# AmbaSat-05-ZMOD4410.net
KiCad netlist of a schematic drawn in EAGLE
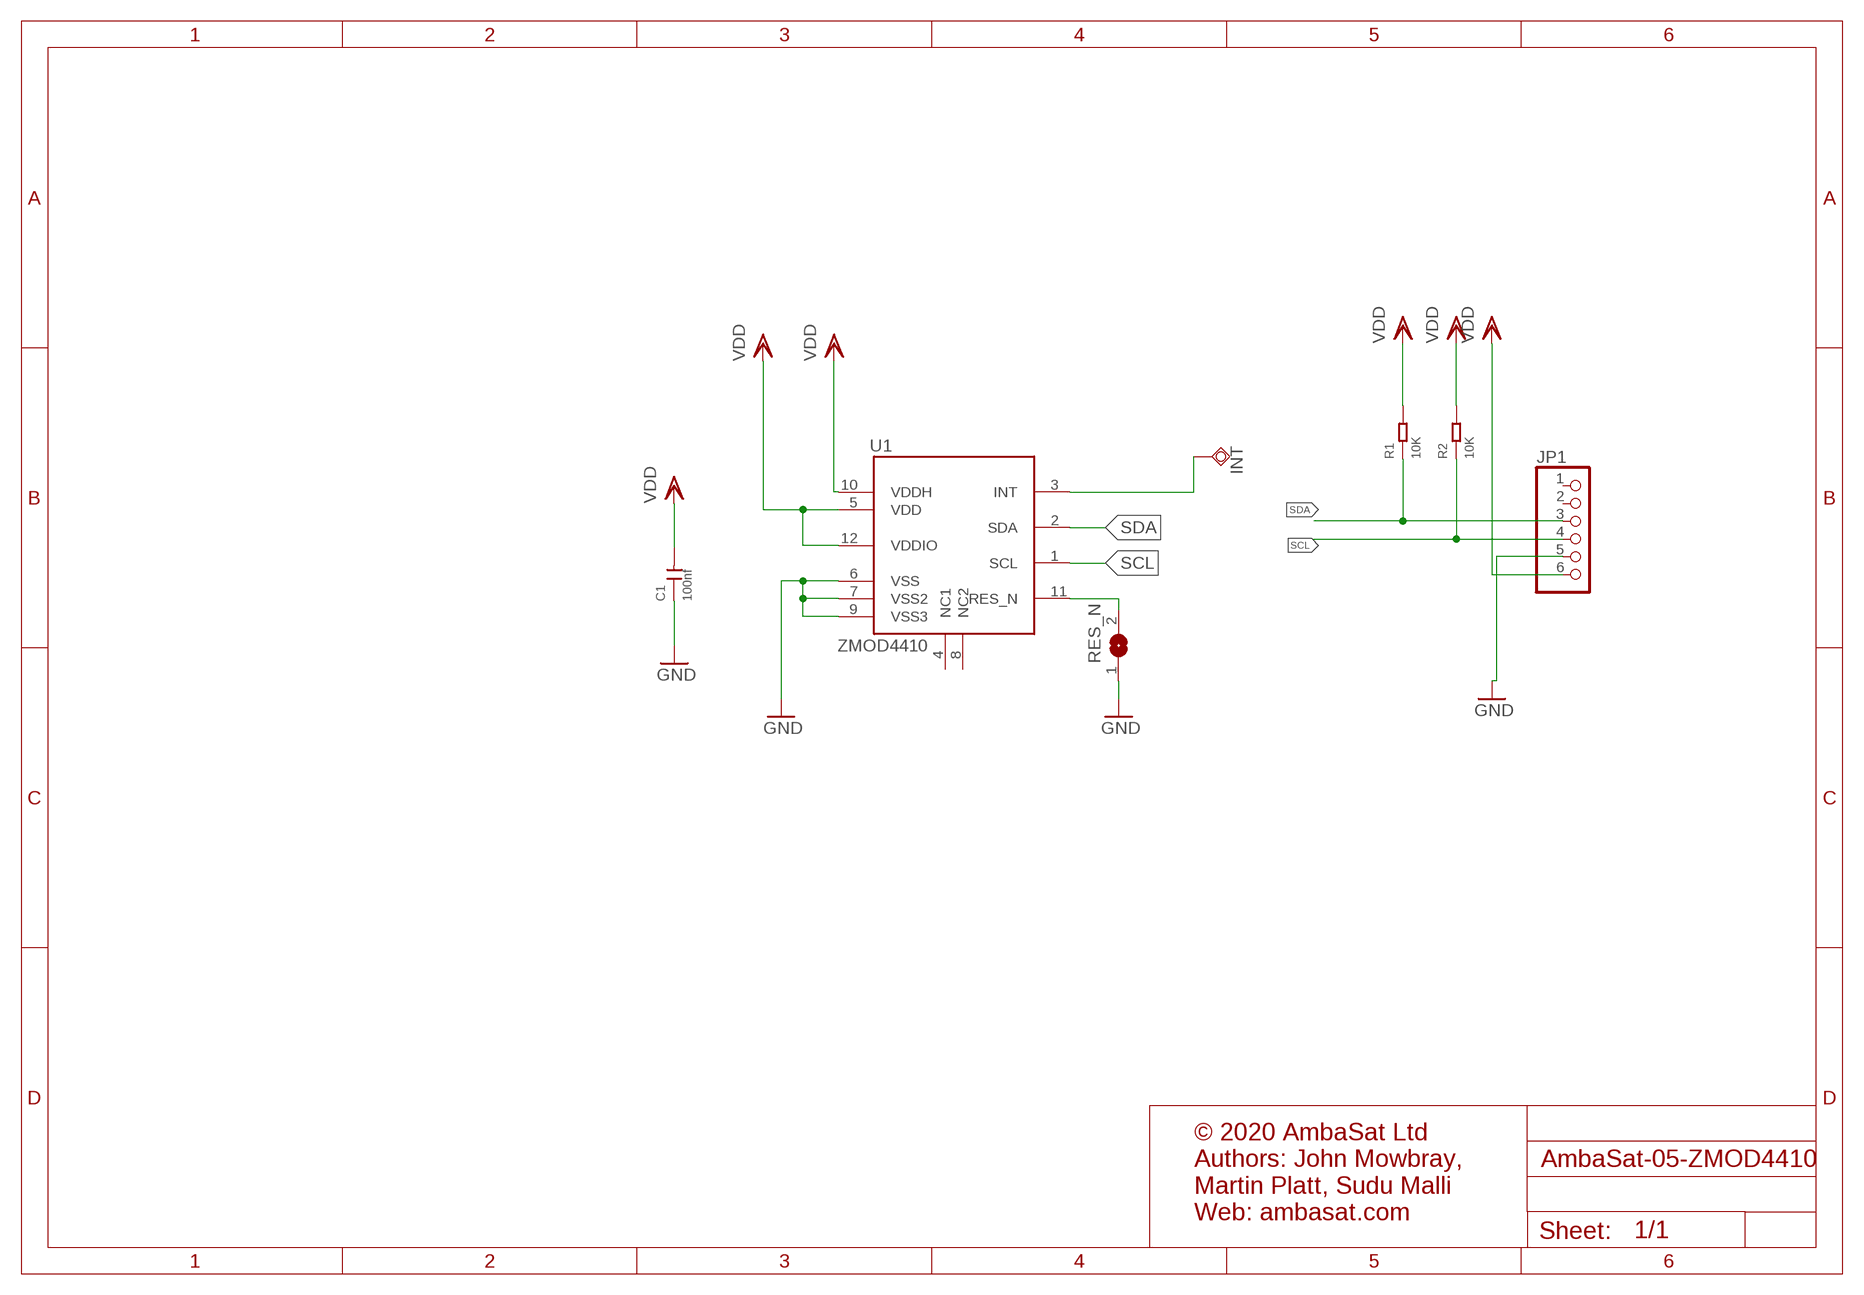
[diagram p0: schematic, sheet 1]

(export (version "E")
  (design (tool "Eeschema 10.0.6"))
  (components
    (comp (ref "C1")
      (value "100nf")
      (footprint "eagle-import:C0805")
      (fields (field (name "MPN") "CC0805KRX7R9BB104"))
      (libsource (lib "eagle-import") (part "CERAMIC-100NF-50V-10%-X7R(0805)"))
    )
    (comp (ref "INT")
      (value "TESTPAD_TPSQTP12R")
      (footprint "eagle-import:TESTPAD_TP12R")
      (libsource (lib "eagle-import") (part "TESTPAD_TPSQTP12R"))
    )
    (comp (ref "JP1")
      (value "HEADER-1X6")
      (footprint "eagle-import:1X06_OVAL")
      (libsource (lib "eagle-import") (part "HEADER-1X6"))
    )
    (comp (ref "R1")
      (value "10K")
      (footprint "eagle-import:R0805")
      (fields (field (name "MPN") "RC0805FR-0710KL"))
      (libsource (lib "eagle-import") (part "SMD-RES-10K-1%-1/8W(0805)"))
    )
    (comp (ref "R2")
      (value "10K")
      (footprint "eagle-import:R0805")
      (fields (field (name "MPN") "RC0805FR-0710KL"))
      (libsource (lib "eagle-import") (part "SMD-RES-10K-1%-1/8W(0805)"))
    )
    (comp (ref "RES_N")
      (value "SJ")
      (footprint "eagle-import:SJ")
      (libsource (lib "eagle-import") (part "SJ"))
    )
    (comp (ref "U1")
      (value "ZMOD4410")
      (footprint "eagle-import:LGG12D1_3X3X0.7_0.5X1")
      (fields
        (field (name "MANUFACTURER") "IDT, Integrated Device Technology Inc")
        (field (name "MPN") "ZMOD4410AI1V")
      )
      (libsource (lib "eagle-import") (part "ZMOD4410"))
    )
  )
  (nets
    (net (code "1") (name "GND") (class "Default")
      (node (ref "C1") (pin "1") (pinfunction "1_1") (pintype "passive"))
      (node (ref "JP1") (pin "5") (pinfunction "5_5") (pintype "passive"))
      (node (ref "RES_N") (pin "1") (pinfunction "1_1") (pintype "passive"))
      (node (ref "U1") (pin "6") (pinfunction "VSS_6") (pintype "power_in"))
      (node (ref "U1") (pin "7") (pinfunction "VSS2_7") (pintype "bidirectional"))
      (node (ref "U1") (pin "9") (pinfunction "VSS3_9") (pintype "bidirectional"))
    )
    (net (code "2") (name "Net-(U1-INT)") (class "Default")
      (node (ref "INT") (pin "TP") (pinfunction "TP_TP") (pintype "input"))
      (node (ref "U1") (pin "3") (pinfunction "INT_3") (pintype "bidirectional"))
    )
    (net (code "3") (name "Net-(U1-RES_N)") (class "Default")
      (node (ref "RES_N") (pin "2") (pinfunction "2_2") (pintype "passive"))
      (node (ref "U1") (pin "11") (pinfunction "RES_N_11") (pintype "bidirectional"))
    )
    (net (code "4") (name "SCL") (class "Default")
      (node (ref "JP1") (pin "4") (pinfunction "4_4") (pintype "passive"))
      (node (ref "R2") (pin "1") (pinfunction "1_1") (pintype "passive"))
      (node (ref "U1") (pin "1") (pinfunction "SCL_1") (pintype "input"))
    )
    (net (code "5") (name "SDA") (class "Default")
      (node (ref "JP1") (pin "3") (pinfunction "3_3") (pintype "passive"))
      (node (ref "R1") (pin "1") (pinfunction "1_1") (pintype "passive"))
      (node (ref "U1") (pin "2") (pinfunction "SDA_2") (pintype "bidirectional"))
    )
    (net (code "6") (name "VDD") (class "Default")
      (node (ref "C1") (pin "2") (pinfunction "2_2") (pintype "passive"))
      (node (ref "JP1") (pin "6") (pinfunction "6_6") (pintype "passive"))
      (node (ref "R1") (pin "2") (pinfunction "2_2") (pintype "passive"))
      (node (ref "R2") (pin "2") (pinfunction "2_2") (pintype "passive"))
      (node (ref "U1") (pin "10") (pinfunction "VDDH_10") (pintype "bidirectional"))
      (node (ref "U1") (pin "12") (pinfunction "VDDIO_12") (pintype "power_in"))
      (node (ref "U1") (pin "5") (pinfunction "VDD_5") (pintype "power_in"))
    )
    (net (code "7") (name "unconnected-(JP1-Pad1)") (class "Default")
      (node (ref "JP1") (pin "1") (pinfunction "1_1") (pintype "passive"))
    )
    (net (code "8") (name "unconnected-(JP1-Pad2)") (class "Default")
      (node (ref "JP1") (pin "2") (pinfunction "2_2") (pintype "passive"))
    )
    (net (code "9") (name "unconnected-(U1-NC1-Pad4)") (class "Default")
      (node (ref "U1") (pin "4") (pinfunction "NC1_4") (pintype "bidirectional"))
    )
    (net (code "10") (name "unconnected-(U1-NC2-Pad8)") (class "Default")
      (node (ref "U1") (pin "8") (pinfunction "NC2_8") (pintype "bidirectional"))
    )
  )
)
